# solar_plant_watering_alarm.net
KiCad netlist of a schematic drawn in Altium Designer
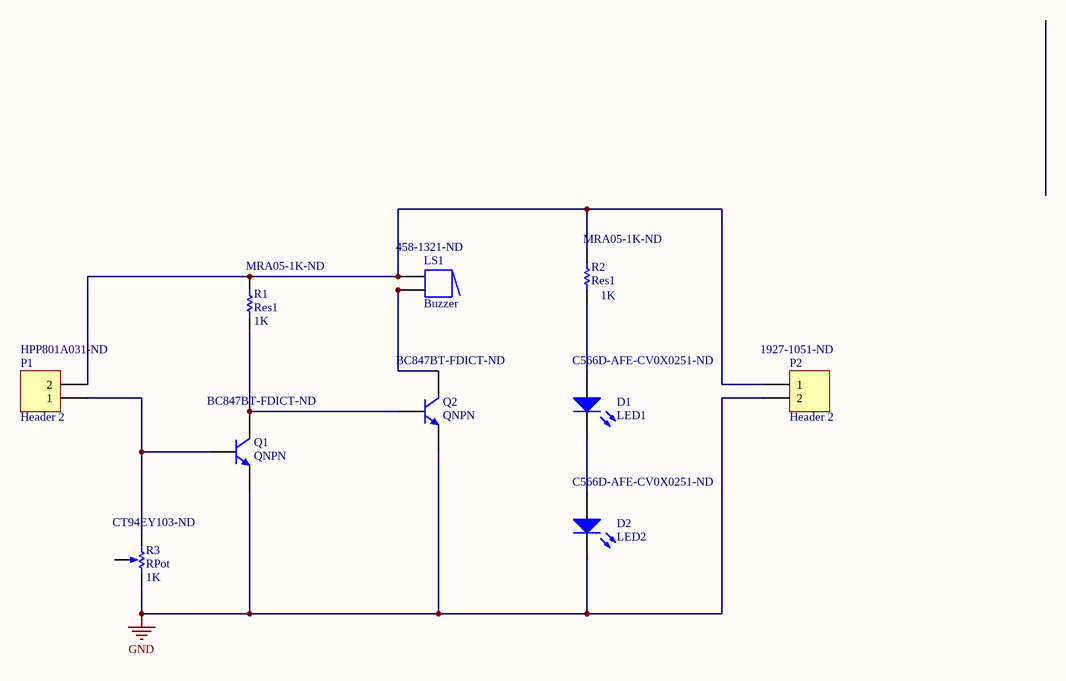
[diagram p0: solar plant watering alarm.SchDoc]

(export (version "E")
  (design (tool "Eeschema 10.0.6"))
  (components
    (comp (ref "D1")
      (value "LED1")
      (footprint "LED-1")
      (description "Typical RED GaAs LED")
      (fields
        (field (name "SUPPLIER PART NUMBER 1") "C566D-AFE-CV0X0251-ND")
        (field (name "PUBLISHER") "Altium Limited")
      )
      (libsource (lib "Miscellaneous Devices") (part "LED1"))
    )
    (comp (ref "D2")
      (value "LED2")
      (footprint "LED-1")
      (description "Typical RED GaAs LED")
      (fields
        (field (name "SUPPLIER PART NUMBER 1") "C566D-AFE-CV0X0251-ND")
        (field (name "PUBLISHER") "Altium Limited")
      )
      (libsource (lib "Miscellaneous Devices") (part "LED1"))
    )
    (comp (ref "LS1")
      (value "Buzzer")
      (footprint "ABSM-1574")
      (description "Magnetic Transducer Buzzer")
      (fields
        (field (name "SUPPLIER PART NUMBER 1") "458-1321-ND")
        (field (name "PUBLISHER") "Altium Limited")
      )
      (libsource (lib "Miscellaneous Devices") (part "Buzzer"))
    )
    (comp (ref "P1")
      (value "Header 2")
      (footprint "HDR1X2")
      (description "Header, 2-Pin")
      (fields
        (field (name "SUPPLIER PART NUMBER 1") "HPP801A031-ND")
        (field (name "PUBLISHER") "Altium Limited")
      )
      (libsource (lib "Miscellaneous Connectors") (part "Header 2"))
    )
    (comp (ref "P2")
      (value "Header 2")
      (footprint "HDR1X2")
      (description "Header, 2-Pin")
      (fields
        (field (name "SUPPLIER PART NUMBER 1") "1927-1051-ND")
        (field (name "PUBLISHER") "Altium Limited")
      )
      (libsource (lib "") (part "Header 2_1"))
    )
    (comp (ref "Q1")
      (value "QNPN")
      (footprint "SOT-23B_N")
      (description "NPN Bipolar Transistor")
      (fields
        (field (name "SUPPLIER PART NUMBER 1") "BC847BT-FDICT-ND")
        (field (name "PUBLISHER") "Altium Limited")
      )
      (libsource (lib "Miscellaneous Devices") (part "QNPN"))
    )
    (comp (ref "Q2")
      (value "QNPN")
      (footprint "SOT-23B_N")
      (description "NPN Bipolar Transistor")
      (fields
        (field (name "SUPPLIER PART NUMBER 1") "BC847BT-FDICT-ND")
        (field (name "PUBLISHER") "Altium Limited")
      )
      (libsource (lib "Miscellaneous Devices") (part "QNPN"))
    )
    (comp (ref "R1")
      (value "Res1")
      (footprint "AXIAL-0.3")
      (description "Resistor")
      (fields
        (field (name "ALTIUM_VALUE") "1K")
        (field (name "SUPPLIER PART NUMBER 1") "MRA05-1K-ND")
        (field (name "PUBLISHER") "Altium Limited")
      )
      (libsource (lib "Miscellaneous Devices") (part "Res1"))
    )
    (comp (ref "R2")
      (value "Res1")
      (footprint "AXIAL-0.3")
      (description "Resistor")
      (fields
        (field (name "ALTIUM_VALUE") "1K")
        (field (name "SUPPLIER PART NUMBER 1") "MRA05-1K-ND")
        (field (name "PUBLISHER") "Altium Limited")
      )
      (libsource (lib "Miscellaneous Devices") (part "Res1"))
    )
    (comp (ref "R3")
      (value "RPot")
      (footprint "VR5")
      (description "Potentiometer")
      (fields
        (field (name "ALTIUM_VALUE") "1K")
        (field (name "SUPPLIER PART NUMBER 1") "CT94EY103-ND")
        (field (name "PUBLISHER") "Altium Limited")
      )
      (libsource (lib "Miscellaneous Devices") (part "RPot"))
    )
  )
  (nets
    (net (code "1") (name "GND") (class "Default")
      (node (ref "D2") (pin "2") (pinfunction "K_2") (pintype "passive"))
      (node (ref "P2") (pin "2") (pinfunction "2_2") (pintype "passive"))
      (node (ref "Q1") (pin "3") (pinfunction "E_3") (pintype "passive"))
      (node (ref "Q2") (pin "3") (pinfunction "E_3") (pintype "passive"))
      (node (ref "R3") (pin "2") (pinfunction "BOT_2") (pintype "passive"))
    )
    (net (code "2") (name "Net-(D1-A)") (class "Default")
      (node (ref "D1") (pin "1") (pinfunction "A_1") (pintype "passive"))
      (node (ref "R2") (pin "1") (pinfunction "1_1") (pintype "passive"))
    )
    (net (code "3") (name "Net-(D1-K)") (class "Default")
      (node (ref "D1") (pin "2") (pinfunction "K_2") (pintype "passive"))
      (node (ref "D2") (pin "1") (pinfunction "A_1") (pintype "passive"))
    )
    (net (code "4") (name "Net-(LS1-Pad1)") (class "Default")
      (node (ref "LS1") (pin "1") (pinfunction "1_1") (pintype "passive"))
      (node (ref "LS1") (pin "1A") (pinfunction "1A_1A") (pintype "passive"))
      (node (ref "P1") (pin "2") (pinfunction "2_2") (pintype "passive"))
      (node (ref "P2") (pin "1") (pinfunction "1_1") (pintype "passive"))
      (node (ref "R1") (pin "2") (pinfunction "2_2") (pintype "passive"))
      (node (ref "R2") (pin "2") (pinfunction "2_2") (pintype "passive"))
    )
    (net (code "5") (name "Net-(Q1-B)") (class "Default")
      (node (ref "P1") (pin "1") (pinfunction "1_1") (pintype "passive"))
      (node (ref "Q1") (pin "2") (pinfunction "B_2") (pintype "passive"))
      (node (ref "R3") (pin "1") (pinfunction "TOP_1") (pintype "passive"))
    )
    (net (code "6") (name "Net-(Q1-C)") (class "Default")
      (node (ref "Q1") (pin "1") (pinfunction "C_1") (pintype "passive"))
      (node (ref "Q2") (pin "2") (pinfunction "B_2") (pintype "passive"))
      (node (ref "R1") (pin "1") (pinfunction "1_1") (pintype "passive"))
    )
    (net (code "7") (name "Net-(Q2-C)") (class "Default")
      (node (ref "LS1") (pin "2") (pinfunction "2_2") (pintype "passive"))
      (node (ref "LS1") (pin "2A") (pinfunction "2A_2A") (pintype "passive"))
      (node (ref "Q2") (pin "1") (pinfunction "C_1") (pintype "passive"))
    )
    (net (code "8") (name "unconnected-(R3-TAP-Pad3)") (class "Default")
      (node (ref "R3") (pin "3") (pinfunction "TAP_3") (pintype "passive"))
    )
  )
)
